# video_switch.net
KiCad netlist of a schematic drawn in Altium Designer
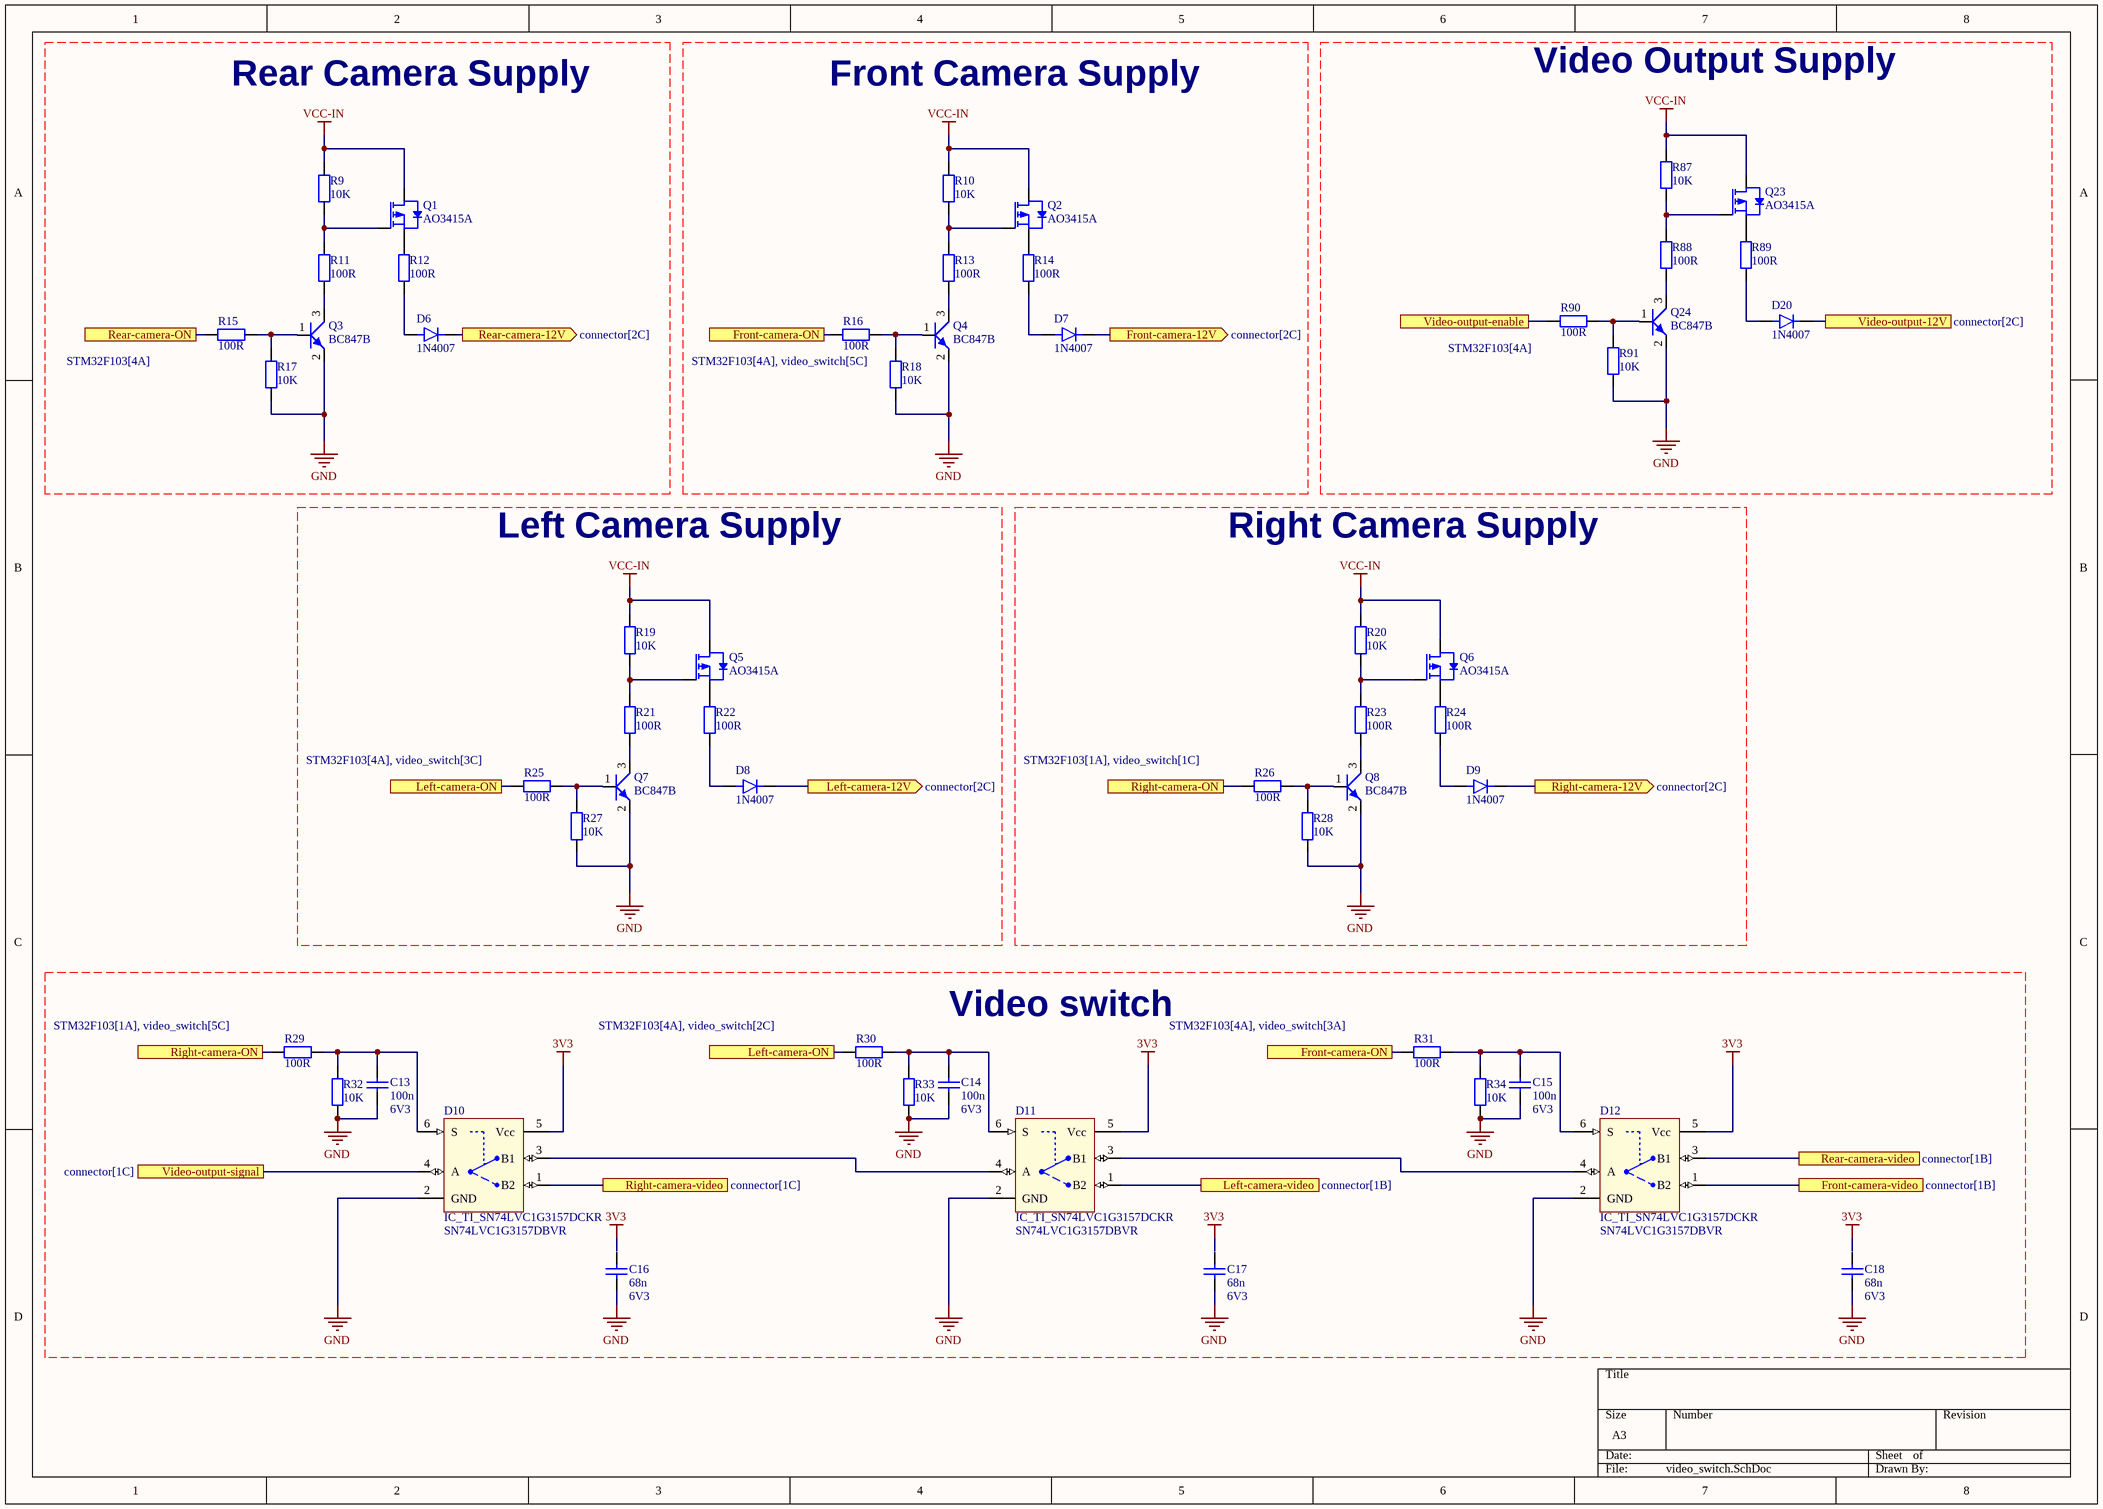
[diagram p0: video_switch.SchDoc]

(export (version "E")
  (design (tool "Eeschema 10.0.6"))
  (components
    (comp (ref "C13")
      (value "CAP")
      (footprint "CAPC2012X88N")
      (description "X7R 10% 0805")
      (fields
        (field (name "VALUE1") "100n")
        (field (name "VALUE2") "6V3")
        (field (name "MANUFACTURER") "KEMET")
      )
      (libsource (lib "DSW_Lib") (part "CAP"))
    )
    (comp (ref "C14")
      (value "CAP")
      (footprint "CAPC2012X88N")
      (description "X7R 10% 0805")
      (fields
        (field (name "VALUE1") "100n")
        (field (name "VALUE2") "6V3")
        (field (name "MANUFACTURER") "KEMET")
      )
      (libsource (lib "DSW_Lib") (part "CAP"))
    )
    (comp (ref "C15")
      (value "CAP")
      (footprint "CAPC2012X88N")
      (description "X7R 10% 0805")
      (fields
        (field (name "VALUE1") "100n")
        (field (name "VALUE2") "6V3")
        (field (name "MANUFACTURER") "KEMET")
      )
      (libsource (lib "DSW_Lib") (part "CAP"))
    )
    (comp (ref "C16")
      (value "CAP")
      (footprint "CAPC2012X100N")
      (description "X7R 10% 0805")
      (fields
        (field (name "VALUE1") "68n")
        (field (name "VALUE2") "6V3")
        (field (name "MANUFACTURER") "KEMET")
      )
      (libsource (lib "DSW_Lib") (part "CAP"))
    )
    (comp (ref "C17")
      (value "CAP")
      (footprint "CAPC2012X100N")
      (description "X7R 10% 0805")
      (fields
        (field (name "VALUE1") "68n")
        (field (name "VALUE2") "6V3")
        (field (name "MANUFACTURER") "KEMET")
      )
      (libsource (lib "DSW_Lib") (part "CAP"))
    )
    (comp (ref "C18")
      (value "CAP")
      (footprint "CAPC2012X100N")
      (description "X7R 10% 0805")
      (fields
        (field (name "VALUE1") "68n")
        (field (name "VALUE2") "6V3")
        (field (name "MANUFACTURER") "KEMET")
      )
      (libsource (lib "DSW_Lib") (part "CAP"))
    )
    (comp (ref "D6")
      (value "DIO")
      (footprint "DO-214AC")
      (description "M7 Diode, max 30A")
      (fields (field (name "VALUE1") "1N4007"))
      (libsource (lib "DSW_Lib") (part "DIO"))
    )
    (comp (ref "D7")
      (value "DIO")
      (footprint "DO-214AC")
      (description "M7 Diode, max 30A")
      (fields (field (name "VALUE1") "1N4007"))
      (libsource (lib "DSW_Lib") (part "DIO"))
    )
    (comp (ref "D8")
      (value "DIO")
      (footprint "DO-214AC")
      (description "M7 Diode, max 30A")
      (fields (field (name "VALUE1") "1N4007"))
      (libsource (lib "DSW_Lib") (part "DIO"))
    )
    (comp (ref "D9")
      (value "DIO")
      (footprint "DO-214AC")
      (description "M7 Diode, max 30A")
      (fields (field (name "VALUE1") "1N4007"))
      (libsource (lib "DSW_Lib") (part "DIO"))
    )
    (comp (ref "D10")
      (value "IC_TI_SN74LVC1G3157DCKR")
      (footprint "SOT23-6N")
      (description "Single-Pole Double-Throw Analog Switch")
      (fields (field (name "VALUE1") "SN74LVC1G3157DBVR") (field (name "MANUFACTURER") "TI"))
      (libsource (lib "DSW_Lib") (part "IC_TI_SN74LVC1G3157DCKR"))
    )
    (comp (ref "D11")
      (value "IC_TI_SN74LVC1G3157DCKR")
      (footprint "SOT23-6N")
      (description "Single-Pole Double-Throw Analog Switch")
      (fields (field (name "VALUE1") "SN74LVC1G3157DBVR") (field (name "MANUFACTURER") "TI"))
      (libsource (lib "DSW_Lib") (part "IC_TI_SN74LVC1G3157DCKR"))
    )
    (comp (ref "D12")
      (value "IC_TI_SN74LVC1G3157DCKR")
      (footprint "SOT23-6N")
      (description "Single-Pole Double-Throw Analog Switch")
      (fields (field (name "VALUE1") "SN74LVC1G3157DBVR") (field (name "MANUFACTURER") "TI"))
      (libsource (lib "DSW_Lib") (part "IC_TI_SN74LVC1G3157DCKR"))
    )
    (comp (ref "D20")
      (value "DIO")
      (footprint "DO-214AC")
      (description "M7 Diode, max 30A")
      (fields (field (name "VALUE1") "1N4007"))
      (libsource (lib "DSW_Lib") (part "DIO"))
    )
    (comp (ref "Q1")
      (value "TRS_FETP_123")
      (footprint "SOT23")
      (description "20V P-Channel MOSFET")
      (fields (field (name "VALUE1") "AO3415A") (field (name "MANUFACTURER") "Alpha & Omega"))
      (libsource (lib "DSW_Lib") (part "TRS_FETP_123"))
    )
    (comp (ref "Q2")
      (value "TRS_FETP_123")
      (footprint "SOT23")
      (description "20V P-Channel MOSFET")
      (fields (field (name "VALUE1") "AO3415A") (field (name "MANUFACTURER") "Alpha & Omega"))
      (libsource (lib "DSW_Lib") (part "TRS_FETP_123"))
    )
    (comp (ref "Q3")
      (value "TRS_NPN_123")
      (footprint "SOT23")
      (description "Bipolar Transistors - BJT NPN 45V 100mA")
      (fields (field (name "VALUE1") "BC847B") (field (name "MANUFACTURER") "NXP"))
      (libsource (lib "DSW_Lib") (part "TRS_NPN_123"))
    )
    (comp (ref "Q4")
      (value "TRS_NPN_123")
      (footprint "SOT23")
      (description "Bipolar Transistors - BJT NPN 45V 100mA")
      (fields (field (name "VALUE1") "BC847B") (field (name "MANUFACTURER") "NXP"))
      (libsource (lib "DSW_Lib") (part "TRS_NPN_123"))
    )
    (comp (ref "Q5")
      (value "TRS_FETP_123")
      (footprint "SOT23")
      (description "20V P-Channel MOSFET")
      (fields (field (name "VALUE1") "AO3415A") (field (name "MANUFACTURER") "Alpha & Omega"))
      (libsource (lib "DSW_Lib") (part "TRS_FETP_123"))
    )
    (comp (ref "Q6")
      (value "TRS_FETP_123")
      (footprint "SOT23")
      (description "20V P-Channel MOSFET")
      (fields (field (name "VALUE1") "AO3415A") (field (name "MANUFACTURER") "Alpha & Omega"))
      (libsource (lib "DSW_Lib") (part "TRS_FETP_123"))
    )
    (comp (ref "Q7")
      (value "TRS_NPN_123")
      (footprint "SOT23")
      (description "Bipolar Transistors - BJT NPN 45V 100mA")
      (fields (field (name "VALUE1") "BC847B") (field (name "MANUFACTURER") "NXP"))
      (libsource (lib "DSW_Lib") (part "TRS_NPN_123"))
    )
    (comp (ref "Q8")
      (value "TRS_NPN_123")
      (footprint "SOT23")
      (description "Bipolar Transistors - BJT NPN 45V 100mA")
      (fields (field (name "VALUE1") "BC847B") (field (name "MANUFACTURER") "NXP"))
      (libsource (lib "DSW_Lib") (part "TRS_NPN_123"))
    )
    (comp (ref "Q23")
      (value "TRS_FETP_123")
      (footprint "SOT23")
      (description "20V P-Channel MOSFET")
      (fields (field (name "VALUE1") "AO3415A") (field (name "MANUFACTURER") "Alpha & Omega"))
      (libsource (lib "DSW_Lib") (part "TRS_FETP_123"))
    )
    (comp (ref "Q24")
      (value "TRS_NPN_123")
      (footprint "SOT23")
      (description "Bipolar Transistors - BJT NPN 45V 100mA")
      (fields (field (name "VALUE1") "BC847B") (field (name "MANUFACTURER") "NXP"))
      (libsource (lib "DSW_Lib") (part "TRS_NPN_123"))
    )
    (comp (ref "R9")
      (value "RES")
      (footprint "RESC2012X60N")
      (description "RESISTOR, 0805, 10K, 1%, SMD")
      (fields (field (name "VALUE1") "10K") (field (name "MANUFACTURER") "Yageo"))
      (libsource (lib "") (part "RES_1"))
    )
    (comp (ref "R10")
      (value "RES")
      (footprint "RESC2012X60N")
      (description "RESISTOR, 0805, 10K, 1%, SMD")
      (fields (field (name "VALUE1") "10K") (field (name "MANUFACTURER") "Yageo"))
      (libsource (lib "") (part "RES_1"))
    )
    (comp (ref "R11")
      (value "RES")
      (footprint "RESC2012X60N")
      (description "RESISTOR, 0805, 100R, 1%, SMD")
      (fields (field (name "VALUE1") "100R") (field (name "MANUFACTURER") "Yageo"))
      (libsource (lib "") (part "RES_1"))
    )
    (comp (ref "R12")
      (value "RES")
      (footprint "RESC2012X60N")
      (description "RESISTOR, 0805, 100R, 1%, SMD")
      (fields (field (name "VALUE1") "100R") (field (name "MANUFACTURER") "Yageo"))
      (libsource (lib "") (part "RES_1"))
    )
    (comp (ref "R13")
      (value "RES")
      (footprint "RESC2012X60N")
      (description "RESISTOR, 0805, 100R, 1%, SMD")
      (fields (field (name "VALUE1") "100R") (field (name "MANUFACTURER") "Yageo"))
      (libsource (lib "") (part "RES_1"))
    )
    (comp (ref "R14")
      (value "RES")
      (footprint "RESC2012X60N")
      (description "RESISTOR, 0805, 100R, 1%, SMD")
      (fields (field (name "VALUE1") "100R") (field (name "MANUFACTURER") "Yageo"))
      (libsource (lib "") (part "RES_1"))
    )
    (comp (ref "R15")
      (value "RES")
      (footprint "RESC2012X60N")
      (description "RESISTOR, 0805, 100R, 1%, SMD")
      (fields (field (name "VALUE1") "100R") (field (name "MANUFACTURER") "Yageo"))
      (libsource (lib "DSW_Lib") (part "RES"))
    )
    (comp (ref "R16")
      (value "RES")
      (footprint "RESC2012X60N")
      (description "RESISTOR, 0805, 100R, 1%, SMD")
      (fields (field (name "VALUE1") "100R") (field (name "MANUFACTURER") "Yageo"))
      (libsource (lib "DSW_Lib") (part "RES"))
    )
    (comp (ref "R17")
      (value "RES")
      (footprint "RESC2012X60N")
      (description "RESISTOR, 0805, 10K, 1%, SMD")
      (fields (field (name "VALUE1") "10K") (field (name "MANUFACTURER") "Yageo"))
      (libsource (lib "") (part "RES_1"))
    )
    (comp (ref "R18")
      (value "RES")
      (footprint "RESC2012X60N")
      (description "RESISTOR, 0805, 10K, 1%, SMD")
      (fields (field (name "VALUE1") "10K") (field (name "MANUFACTURER") "Yageo"))
      (libsource (lib "") (part "RES_1"))
    )
    (comp (ref "R19")
      (value "RES")
      (footprint "RESC2012X60N")
      (description "RESISTOR, 0805, 10K, 1%, SMD")
      (fields (field (name "VALUE1") "10K") (field (name "MANUFACTURER") "Yageo"))
      (libsource (lib "") (part "RES_1"))
    )
    (comp (ref "R20")
      (value "RES")
      (footprint "RESC2012X60N")
      (description "RESISTOR, 0805, 10K, 1%, SMD")
      (fields (field (name "VALUE1") "10K") (field (name "MANUFACTURER") "Yageo"))
      (libsource (lib "") (part "RES_1"))
    )
    (comp (ref "R21")
      (value "RES")
      (footprint "RESC2012X60N")
      (description "RESISTOR, 0805, 100R, 1%, SMD")
      (fields (field (name "VALUE1") "100R") (field (name "MANUFACTURER") "Yageo"))
      (libsource (lib "") (part "RES_1"))
    )
    (comp (ref "R22")
      (value "RES")
      (footprint "RESC2012X60N")
      (description "RESISTOR, 0805, 100R, 1%, SMD")
      (fields (field (name "VALUE1") "100R") (field (name "MANUFACTURER") "Yageo"))
      (libsource (lib "") (part "RES_1"))
    )
    (comp (ref "R23")
      (value "RES")
      (footprint "RESC2012X60N")
      (description "RESISTOR, 0805, 100R, 1%, SMD")
      (fields (field (name "VALUE1") "100R") (field (name "MANUFACTURER") "Yageo"))
      (libsource (lib "") (part "RES_1"))
    )
    (comp (ref "R24")
      (value "RES")
      (footprint "RESC2012X60N")
      (description "RESISTOR, 0805, 100R, 1%, SMD")
      (fields (field (name "VALUE1") "100R") (field (name "MANUFACTURER") "Yageo"))
      (libsource (lib "") (part "RES_1"))
    )
    (comp (ref "R25")
      (value "RES")
      (footprint "RESC2012X60N")
      (description "RESISTOR, 0805, 100R, 1%, SMD")
      (fields (field (name "VALUE1") "100R") (field (name "MANUFACTURER") "Yageo"))
      (libsource (lib "DSW_Lib") (part "RES"))
    )
    (comp (ref "R26")
      (value "RES")
      (footprint "RESC2012X60N")
      (description "RESISTOR, 0805, 100R, 1%, SMD")
      (fields (field (name "VALUE1") "100R") (field (name "MANUFACTURER") "Yageo"))
      (libsource (lib "DSW_Lib") (part "RES"))
    )
    (comp (ref "R27")
      (value "RES")
      (footprint "RESC2012X60N")
      (description "RESISTOR, 0805, 10K, 1%, SMD")
      (fields (field (name "VALUE1") "10K") (field (name "MANUFACTURER") "Yageo"))
      (libsource (lib "") (part "RES_1"))
    )
    (comp (ref "R28")
      (value "RES")
      (footprint "RESC2012X60N")
      (description "RESISTOR, 0805, 10K, 1%, SMD")
      (fields (field (name "VALUE1") "10K") (field (name "MANUFACTURER") "Yageo"))
      (libsource (lib "") (part "RES_1"))
    )
    (comp (ref "R29")
      (value "RES")
      (footprint "RESC2012X60N")
      (description "RESISTOR, 0805, 100R, 1%, SMD")
      (fields (field (name "VALUE1") "100R") (field (name "MANUFACTURER") "Yageo"))
      (libsource (lib "DSW_Lib") (part "RES"))
    )
    (comp (ref "R30")
      (value "RES")
      (footprint "RESC2012X60N")
      (description "RESISTOR, 0805, 100R, 1%, SMD")
      (fields (field (name "VALUE1") "100R") (field (name "MANUFACTURER") "Yageo"))
      (libsource (lib "DSW_Lib") (part "RES"))
    )
    (comp (ref "R31")
      (value "RES")
      (footprint "RESC2012X60N")
      (description "RESISTOR, 0805, 100R, 1%, SMD")
      (fields (field (name "VALUE1") "100R") (field (name "MANUFACTURER") "Yageo"))
      (libsource (lib "DSW_Lib") (part "RES"))
    )
    (comp (ref "R32")
      (value "RES")
      (footprint "RESC2012X60N")
      (description "RESISTOR, 0805, 10K, 1%, SMD")
      (fields (field (name "VALUE1") "10K") (field (name "MANUFACTURER") "Yageo"))
      (libsource (lib "") (part "RES_1"))
    )
    (comp (ref "R33")
      (value "RES")
      (footprint "RESC2012X60N")
      (description "RESISTOR, 0805, 10K, 1%, SMD")
      (fields (field (name "VALUE1") "10K") (field (name "MANUFACTURER") "Yageo"))
      (libsource (lib "") (part "RES_1"))
    )
    (comp (ref "R34")
      (value "RES")
      (footprint "RESC2012X60N")
      (description "RESISTOR, 0805, 10K, 1%, SMD")
      (fields (field (name "VALUE1") "10K") (field (name "MANUFACTURER") "Yageo"))
      (libsource (lib "") (part "RES_1"))
    )
    (comp (ref "R87")
      (value "RES")
      (footprint "RESC2012X60N")
      (description "RESISTOR, 0805, 10K, 1%, SMD")
      (fields (field (name "VALUE1") "10K") (field (name "MANUFACTURER") "Yageo"))
      (libsource (lib "") (part "RES_1"))
    )
    (comp (ref "R88")
      (value "RES")
      (footprint "RESC2012X60N")
      (description "RESISTOR, 0805, 100R, 1%, SMD")
      (fields (field (name "VALUE1") "100R") (field (name "MANUFACTURER") "Yageo"))
      (libsource (lib "") (part "RES_1"))
    )
    (comp (ref "R89")
      (value "RES")
      (footprint "RESC2012X60N")
      (description "RESISTOR, 0805, 100R, 1%, SMD")
      (fields (field (name "VALUE1") "100R") (field (name "MANUFACTURER") "Yageo"))
      (libsource (lib "") (part "RES_1"))
    )
    (comp (ref "R90")
      (value "RES")
      (footprint "RESC2012X60N")
      (description "RESISTOR, 0805, 100R, 1%, SMD")
      (fields (field (name "VALUE1") "100R") (field (name "MANUFACTURER") "Yageo"))
      (libsource (lib "DSW_Lib") (part "RES"))
    )
    (comp (ref "R91")
      (value "RES")
      (footprint "RESC2012X60N")
      (description "RESISTOR, 0805, 10K, 1%, SMD")
      (fields (field (name "VALUE1") "10K") (field (name "MANUFACTURER") "Yageo"))
      (libsource (lib "") (part "RES_1"))
    )
  )
  (nets
    (net (code "1") (name "/Front-camera-12V") (class "Default")
      (node (ref "D7") (pin "2") (pinfunction "K_2") (pintype "passive"))
    )
    (net (code "2") (name "/Front-camera-ON") (class "Default")
      (node (ref "R16") (pin "1") (pinfunction "1_1") (pintype "passive"))
      (node (ref "R31") (pin "1") (pinfunction "1_1") (pintype "passive"))
    )
    (net (code "3") (name "/Front-camera-video") (class "Default")
      (node (ref "D12") (pin "1") (pinfunction "B2_1") (pintype "bidirectional"))
    )
    (net (code "4") (name "/Left-camera-12V") (class "Default")
      (node (ref "D8") (pin "2") (pinfunction "K_2") (pintype "passive"))
    )
    (net (code "5") (name "/Left-camera-ON") (class "Default")
      (node (ref "R25") (pin "1") (pinfunction "1_1") (pintype "passive"))
      (node (ref "R30") (pin "1") (pinfunction "1_1") (pintype "passive"))
    )
    (net (code "6") (name "/Left-camera-video") (class "Default")
      (node (ref "D11") (pin "1") (pinfunction "B2_1") (pintype "bidirectional"))
    )
    (net (code "7") (name "/Rear-camera-12V") (class "Default")
      (node (ref "D6") (pin "2") (pinfunction "K_2") (pintype "passive"))
    )
    (net (code "8") (name "/Rear-camera-ON") (class "Default")
      (node (ref "R15") (pin "1") (pinfunction "1_1") (pintype "passive"))
    )
    (net (code "9") (name "/Rear-camera-video") (class "Default")
      (node (ref "D12") (pin "3") (pinfunction "B1_3") (pintype "bidirectional"))
    )
    (net (code "10") (name "/Right-camera-12V") (class "Default")
      (node (ref "D9") (pin "2") (pinfunction "K_2") (pintype "passive"))
    )
    (net (code "11") (name "/Right-camera-ON") (class "Default")
      (node (ref "R26") (pin "1") (pinfunction "1_1") (pintype "passive"))
      (node (ref "R29") (pin "1") (pinfunction "1_1") (pintype "passive"))
    )
    (net (code "12") (name "/Right-camera-video") (class "Default")
      (node (ref "D10") (pin "1") (pinfunction "B2_1") (pintype "bidirectional"))
    )
    (net (code "13") (name "/Video-output-12V") (class "Default")
      (node (ref "D20") (pin "2") (pinfunction "K_2") (pintype "passive"))
    )
    (net (code "14") (name "/Video-output-enable") (class "Default")
      (node (ref "R90") (pin "1") (pinfunction "1_1") (pintype "passive"))
    )
    (net (code "15") (name "/Video-output-signal") (class "Default")
      (node (ref "D10") (pin "4") (pinfunction "A_4") (pintype "bidirectional"))
    )
    (net (code "16") (name "3V3") (class "Default")
      (node (ref "D10") (pin "5") (pinfunction "Vcc_5") (pintype "power_in"))
      (node (ref "D11") (pin "5") (pinfunction "Vcc_5") (pintype "power_in"))
      (node (ref "D12") (pin "5") (pinfunction "Vcc_5") (pintype "power_in"))
    )
    (net (code "17") (name "GND") (class "Default")
      (node (ref "C13") (pin "1") (pinfunction "1_1") (pintype "passive"))
      (node (ref "C14") (pin "1") (pinfunction "1_1") (pintype "passive"))
      (node (ref "C15") (pin "1") (pinfunction "1_1") (pintype "passive"))
      (node (ref "C16") (pin "1") (pinfunction "1_1") (pintype "passive"))
      (node (ref "C17") (pin "1") (pinfunction "1_1") (pintype "passive"))
      (node (ref "C18") (pin "1") (pinfunction "1_1") (pintype "passive"))
      (node (ref "D10") (pin "2") (pinfunction "GND_2") (pintype "power_in"))
      (node (ref "D11") (pin "2") (pinfunction "GND_2") (pintype "power_in"))
      (node (ref "D12") (pin "2") (pinfunction "GND_2") (pintype "power_in"))
      (node (ref "Q24") (pin "2") (pinfunction "E_2") (pintype "passive"))
      (node (ref "Q3") (pin "2") (pinfunction "E_2") (pintype "passive"))
      (node (ref "Q4") (pin "2") (pinfunction "E_2") (pintype "passive"))
      (node (ref "Q7") (pin "2") (pinfunction "E_2") (pintype "passive"))
      (node (ref "Q8") (pin "2") (pinfunction "E_2") (pintype "passive"))
      (node (ref "R17") (pin "1") (pinfunction "1_1") (pintype "passive"))
      (node (ref "R18") (pin "1") (pinfunction "1_1") (pintype "passive"))
      (node (ref "R27") (pin "1") (pinfunction "1_1") (pintype "passive"))
      (node (ref "R28") (pin "1") (pinfunction "1_1") (pintype "passive"))
      (node (ref "R32") (pin "1") (pinfunction "1_1") (pintype "passive"))
      (node (ref "R33") (pin "1") (pinfunction "1_1") (pintype "passive"))
      (node (ref "R34") (pin "1") (pinfunction "1_1") (pintype "passive"))
      (node (ref "R91") (pin "1") (pinfunction "1_1") (pintype "passive"))
    )
    (net (code "18") (name "Net-(D6-A)") (class "Default")
      (node (ref "D6") (pin "1") (pinfunction "A_1") (pintype "passive"))
      (node (ref "R12") (pin "1") (pinfunction "1_1") (pintype "passive"))
    )
    (net (code "19") (name "Net-(D7-A)") (class "Default")
      (node (ref "D7") (pin "1") (pinfunction "A_1") (pintype "passive"))
      (node (ref "R14") (pin "1") (pinfunction "1_1") (pintype "passive"))
    )
    (net (code "20") (name "Net-(D8-A)") (class "Default")
      (node (ref "D8") (pin "1") (pinfunction "A_1") (pintype "passive"))
      (node (ref "R22") (pin "1") (pinfunction "1_1") (pintype "passive"))
    )
    (net (code "21") (name "Net-(D9-A)") (class "Default")
      (node (ref "D9") (pin "1") (pinfunction "A_1") (pintype "passive"))
      (node (ref "R24") (pin "1") (pinfunction "1_1") (pintype "passive"))
    )
    (net (code "22") (name "Net-(D10-B1)") (class "Default")
      (node (ref "D10") (pin "3") (pinfunction "B1_3") (pintype "bidirectional"))
      (node (ref "D11") (pin "4") (pinfunction "A_4") (pintype "bidirectional"))
    )
    (net (code "23") (name "Net-(D10-S)") (class "Default")
      (node (ref "C13") (pin "2") (pinfunction "2_2") (pintype "passive"))
      (node (ref "D10") (pin "6") (pinfunction "S_6") (pintype "input"))
      (node (ref "R29") (pin "2") (pinfunction "2_2") (pintype "passive"))
      (node (ref "R32") (pin "2") (pinfunction "2_2") (pintype "passive"))
    )
    (net (code "24") (name "Net-(D11-B1)") (class "Default")
      (node (ref "D11") (pin "3") (pinfunction "B1_3") (pintype "bidirectional"))
      (node (ref "D12") (pin "4") (pinfunction "A_4") (pintype "bidirectional"))
    )
    (net (code "25") (name "Net-(D11-S)") (class "Default")
      (node (ref "C14") (pin "2") (pinfunction "2_2") (pintype "passive"))
      (node (ref "D11") (pin "6") (pinfunction "S_6") (pintype "input"))
      (node (ref "R30") (pin "2") (pinfunction "2_2") (pintype "passive"))
      (node (ref "R33") (pin "2") (pinfunction "2_2") (pintype "passive"))
    )
    (net (code "26") (name "Net-(D12-S)") (class "Default")
      (node (ref "C15") (pin "2") (pinfunction "2_2") (pintype "passive"))
      (node (ref "D12") (pin "6") (pinfunction "S_6") (pintype "input"))
      (node (ref "R31") (pin "2") (pinfunction "2_2") (pintype "passive"))
      (node (ref "R34") (pin "2") (pinfunction "2_2") (pintype "passive"))
    )
    (net (code "27") (name "Net-(D20-A)") (class "Default")
      (node (ref "D20") (pin "1") (pinfunction "A_1") (pintype "passive"))
      (node (ref "R89") (pin "1") (pinfunction "1_1") (pintype "passive"))
    )
    (net (code "28") (name "Net-(Q1-G)") (class "Default")
      (node (ref "Q1") (pin "1") (pinfunction "G_1") (pintype "passive"))
      (node (ref "R11") (pin "2") (pinfunction "2_2") (pintype "passive"))
      (node (ref "R9") (pin "1") (pinfunction "1_1") (pintype "passive"))
    )
    (net (code "29") (name "Net-(Q1-S)") (class "Default")
      (node (ref "Q1") (pin "2") (pinfunction "S_2") (pintype "passive"))
      (node (ref "R12") (pin "2") (pinfunction "2_2") (pintype "passive"))
    )
    (net (code "30") (name "Net-(Q2-G)") (class "Default")
      (node (ref "Q2") (pin "1") (pinfunction "G_1") (pintype "passive"))
      (node (ref "R10") (pin "1") (pinfunction "1_1") (pintype "passive"))
      (node (ref "R13") (pin "2") (pinfunction "2_2") (pintype "passive"))
    )
    (net (code "31") (name "Net-(Q2-S)") (class "Default")
      (node (ref "Q2") (pin "2") (pinfunction "S_2") (pintype "passive"))
      (node (ref "R14") (pin "2") (pinfunction "2_2") (pintype "passive"))
    )
    (net (code "32") (name "Net-(Q3-B)") (class "Default")
      (node (ref "Q3") (pin "1") (pinfunction "B_1") (pintype "passive"))
      (node (ref "R15") (pin "2") (pinfunction "2_2") (pintype "passive"))
      (node (ref "R17") (pin "2") (pinfunction "2_2") (pintype "passive"))
    )
    (net (code "33") (name "Net-(Q3-C)") (class "Default")
      (node (ref "Q3") (pin "3") (pinfunction "C_3") (pintype "passive"))
      (node (ref "R11") (pin "1") (pinfunction "1_1") (pintype "passive"))
    )
    (net (code "34") (name "Net-(Q4-B)") (class "Default")
      (node (ref "Q4") (pin "1") (pinfunction "B_1") (pintype "passive"))
      (node (ref "R16") (pin "2") (pinfunction "2_2") (pintype "passive"))
      (node (ref "R18") (pin "2") (pinfunction "2_2") (pintype "passive"))
    )
    (net (code "35") (name "Net-(Q4-C)") (class "Default")
      (node (ref "Q4") (pin "3") (pinfunction "C_3") (pintype "passive"))
      (node (ref "R13") (pin "1") (pinfunction "1_1") (pintype "passive"))
    )
    (net (code "36") (name "Net-(Q5-G)") (class "Default")
      (node (ref "Q5") (pin "1") (pinfunction "G_1") (pintype "passive"))
      (node (ref "R19") (pin "1") (pinfunction "1_1") (pintype "passive"))
      (node (ref "R21") (pin "2") (pinfunction "2_2") (pintype "passive"))
    )
    (net (code "37") (name "Net-(Q5-S)") (class "Default")
      (node (ref "Q5") (pin "2") (pinfunction "S_2") (pintype "passive"))
      (node (ref "R22") (pin "2") (pinfunction "2_2") (pintype "passive"))
    )
    (net (code "38") (name "Net-(Q6-G)") (class "Default")
      (node (ref "Q6") (pin "1") (pinfunction "G_1") (pintype "passive"))
      (node (ref "R20") (pin "1") (pinfunction "1_1") (pintype "passive"))
      (node (ref "R23") (pin "2") (pinfunction "2_2") (pintype "passive"))
    )
    (net (code "39") (name "Net-(Q6-S)") (class "Default")
      (node (ref "Q6") (pin "2") (pinfunction "S_2") (pintype "passive"))
      (node (ref "R24") (pin "2") (pinfunction "2_2") (pintype "passive"))
    )
    (net (code "40") (name "Net-(Q7-B)") (class "Default")
      (node (ref "Q7") (pin "1") (pinfunction "B_1") (pintype "passive"))
      (node (ref "R25") (pin "2") (pinfunction "2_2") (pintype "passive"))
      (node (ref "R27") (pin "2") (pinfunction "2_2") (pintype "passive"))
    )
    (net (code "41") (name "Net-(Q7-C)") (class "Default")
      (node (ref "Q7") (pin "3") (pinfunction "C_3") (pintype "passive"))
      (node (ref "R21") (pin "1") (pinfunction "1_1") (pintype "passive"))
    )
    (net (code "42") (name "Net-(Q8-B)") (class "Default")
      (node (ref "Q8") (pin "1") (pinfunction "B_1") (pintype "passive"))
      (node (ref "R26") (pin "2") (pinfunction "2_2") (pintype "passive"))
      (node (ref "R28") (pin "2") (pinfunction "2_2") (pintype "passive"))
    )
    (net (code "43") (name "Net-(Q8-C)") (class "Default")
      (node (ref "Q8") (pin "3") (pinfunction "C_3") (pintype "passive"))
      (node (ref "R23") (pin "1") (pinfunction "1_1") (pintype "passive"))
    )
    (net (code "44") (name "Net-(Q23-G)") (class "Default")
      (node (ref "Q23") (pin "1") (pinfunction "G_1") (pintype "passive"))
      (node (ref "R87") (pin "1") (pinfunction "1_1") (pintype "passive"))
      (node (ref "R88") (pin "2") (pinfunction "2_2") (pintype "passive"))
    )
    (net (code "45") (name "Net-(Q23-S)") (class "Default")
      (node (ref "Q23") (pin "2") (pinfunction "S_2") (pintype "passive"))
      (node (ref "R89") (pin "2") (pinfunction "2_2") (pintype "passive"))
    )
    (net (code "46") (name "Net-(Q24-B)") (class "Default")
      (node (ref "Q24") (pin "1") (pinfunction "B_1") (pintype "passive"))
      (node (ref "R90") (pin "2") (pinfunction "2_2") (pintype "passive"))
      (node (ref "R91") (pin "2") (pinfunction "2_2") (pintype "passive"))
    )
    (net (code "47") (name "Net-(Q24-C)") (class "Default")
      (node (ref "Q24") (pin "3") (pinfunction "C_3") (pintype "passive"))
      (node (ref "R88") (pin "1") (pinfunction "1_1") (pintype "passive"))
    )
    (net (code "48") (name "VCC-IN") (class "Default")
      (node (ref "Q1") (pin "3") (pinfunction "D_3") (pintype "passive"))
      (node (ref "Q2") (pin "3") (pinfunction "D_3") (pintype "passive"))
      (node (ref "Q23") (pin "3") (pinfunction "D_3") (pintype "passive"))
      (node (ref "Q5") (pin "3") (pinfunction "D_3") (pintype "passive"))
      (node (ref "Q6") (pin "3") (pinfunction "D_3") (pintype "passive"))
      (node (ref "R10") (pin "2") (pinfunction "2_2") (pintype "passive"))
      (node (ref "R19") (pin "2") (pinfunction "2_2") (pintype "passive"))
      (node (ref "R20") (pin "2") (pinfunction "2_2") (pintype "passive"))
      (node (ref "R87") (pin "2") (pinfunction "2_2") (pintype "passive"))
      (node (ref "R9") (pin "2") (pinfunction "2_2") (pintype "passive"))
    )
    (net (code "49") (name "unconnected-(C16-Pad2)") (class "Default")
      (node (ref "C16") (pin "2") (pinfunction "2_2") (pintype "passive"))
    )
    (net (code "50") (name "unconnected-(C17-Pad2)") (class "Default")
      (node (ref "C17") (pin "2") (pinfunction "2_2") (pintype "passive"))
    )
    (net (code "51") (name "unconnected-(C18-Pad2)") (class "Default")
      (node (ref "C18") (pin "2") (pinfunction "2_2") (pintype "passive"))
    )
  )
)
